# ProPrj_ProDocument_Button_Board_v3_0_202.net
KiCad netlist of a schematic drawn in EasyEDA Pro
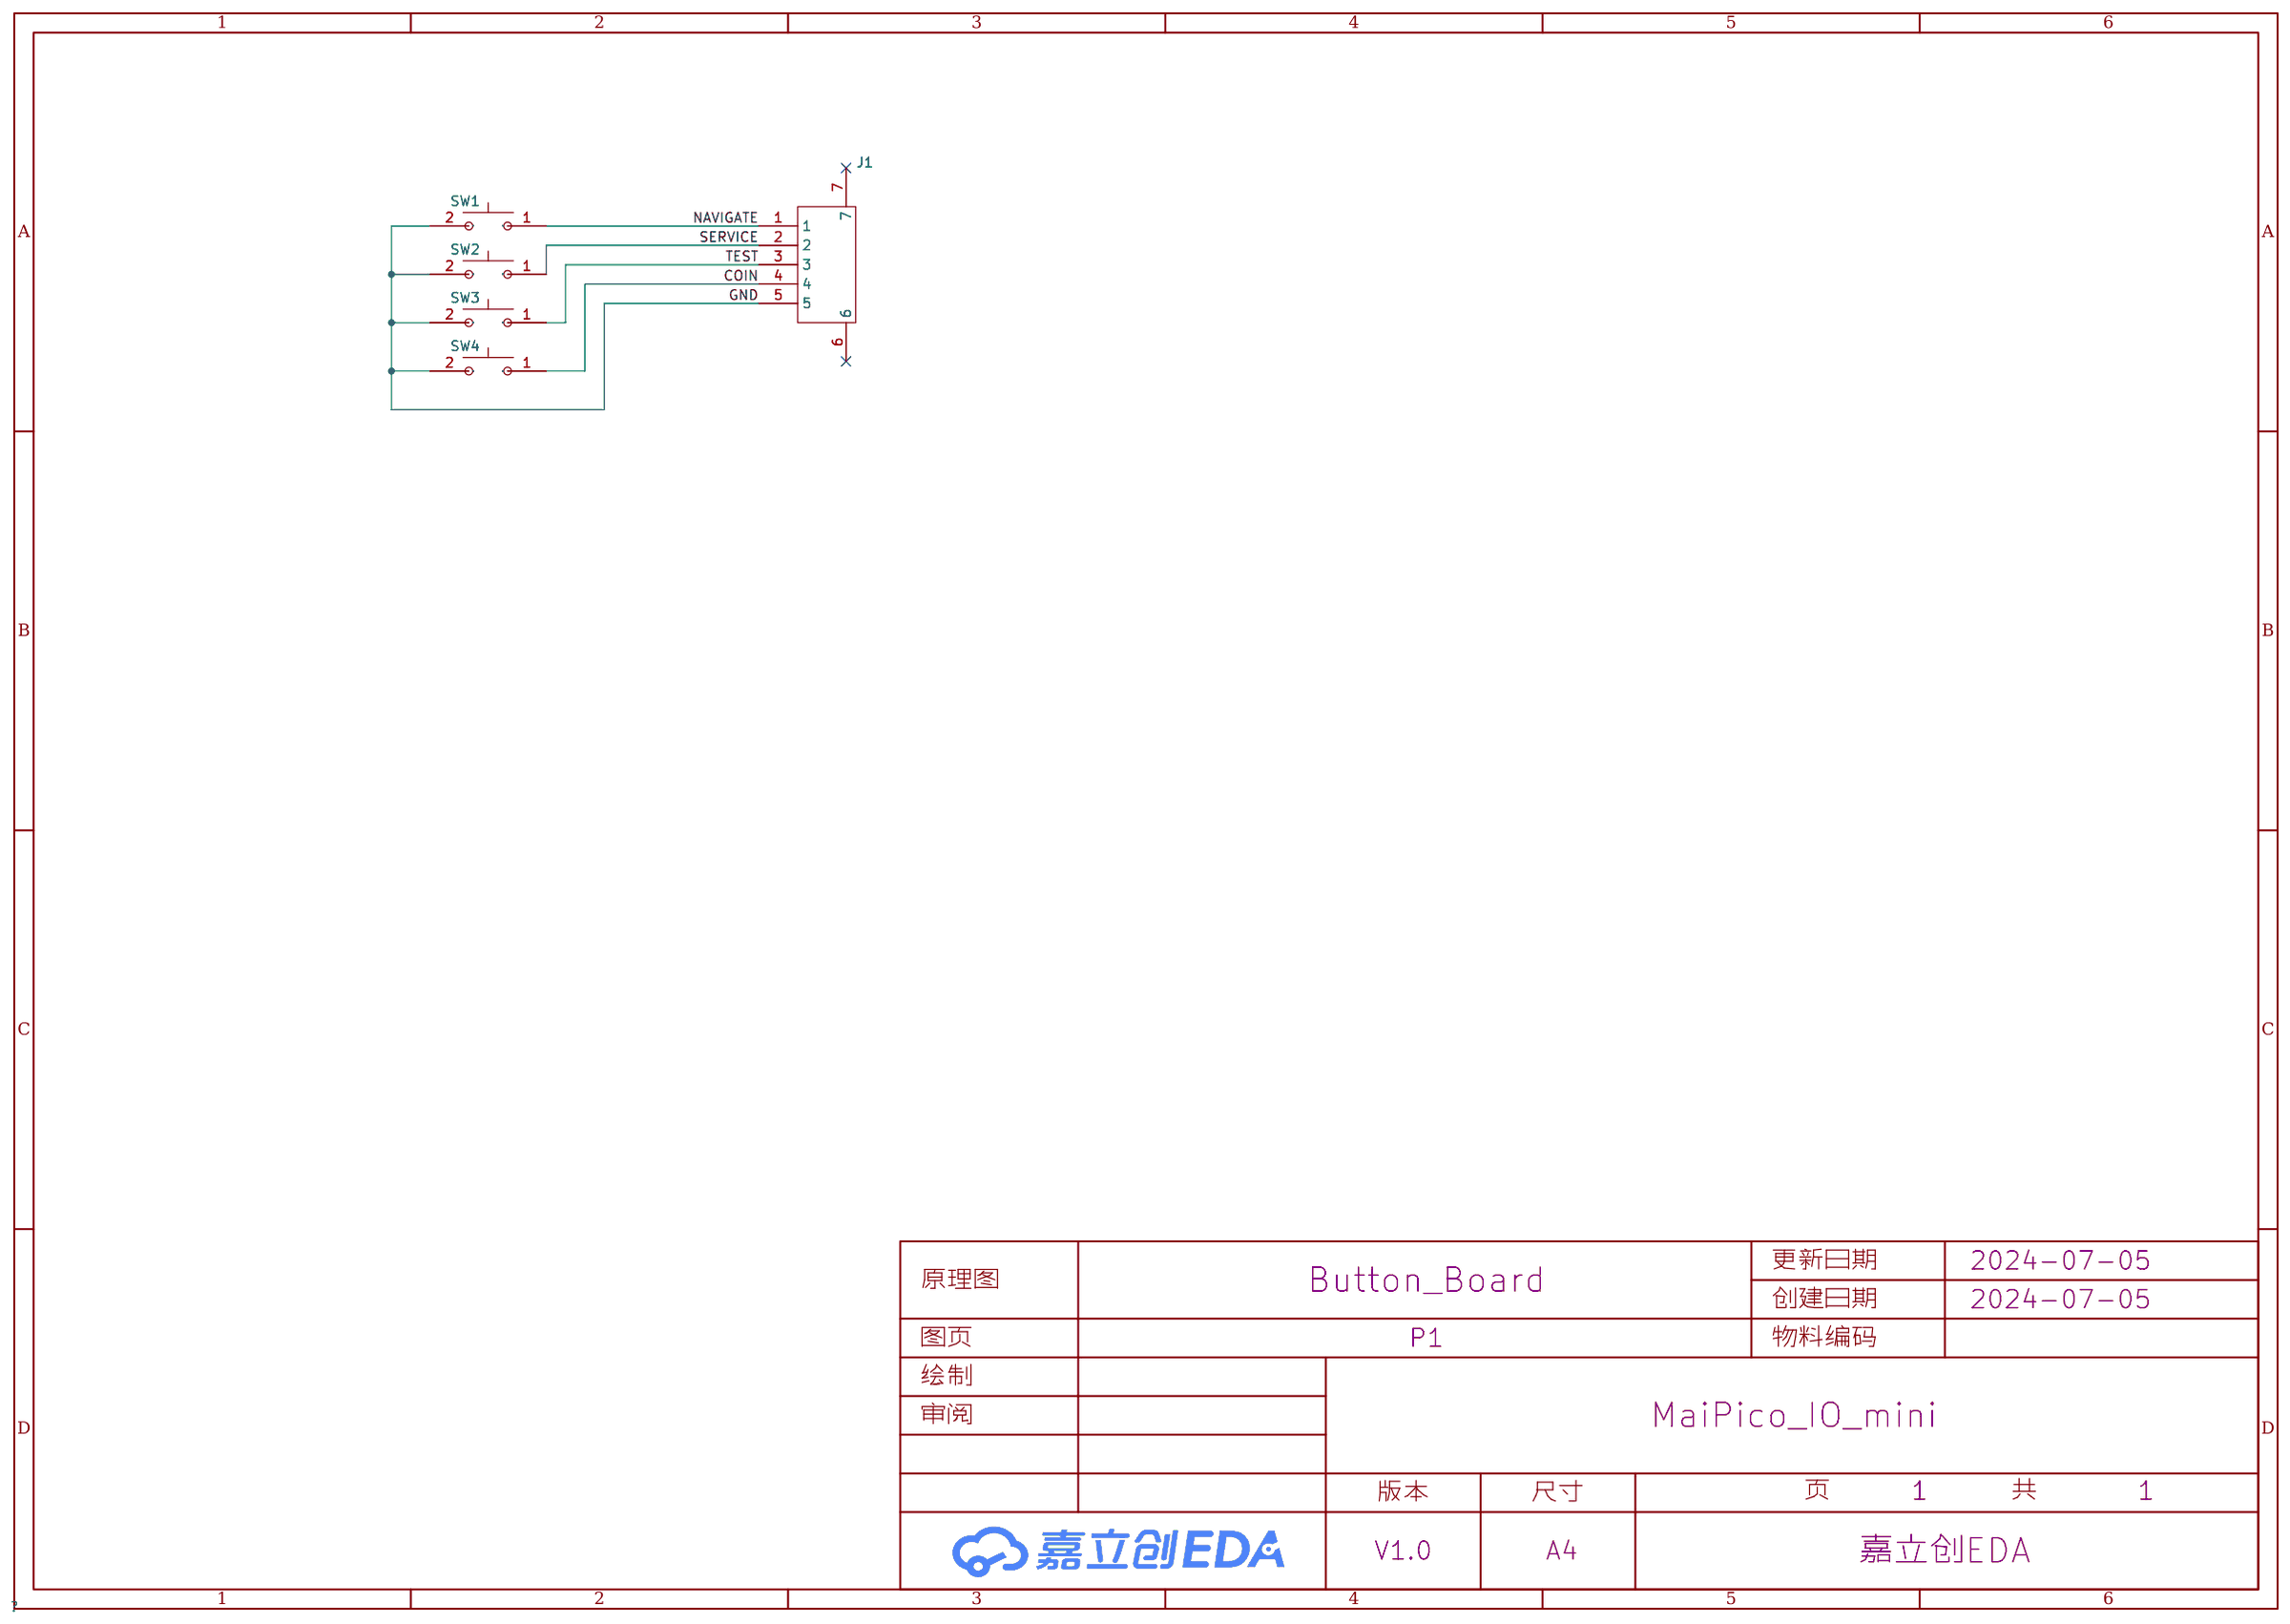
[diagram p0: schematic sheet]

(export (version "E")
  (design (tool "Eeschema 10.0.6"))
  (components
    (comp (ref "J1")
      (value "AFA01-S05FCC-00")
      (footprint "easyedapro:FPC-SMD_P1.00-5P_FGS-XJ-H2.0")
      (description "锁定特性:翻盖式;触点类型:下接;触点数量:5P;间距:1mm;安装类型:卧贴;")
      (fields (field (name "Manufacturer") "JS(钜硕电子)"))
      (libsource (lib "easyedapro") (part "AFA01-S05FCC-00"))
    )
    (comp (ref "SW1")
      (value "1TS009B-2500-5000-CT")
      (footprint "easyedapro:SW-SMD_L6.0-W6.0-P6.00-LS6.6")
      (fields (field (name "Manufacturer") "HYP(鸿源精密)"))
      (libsource (lib "easyedapro") (part "1TS009B-2500-5000"))
    )
    (comp (ref "SW2")
      (value "1TS009B-2500-5000-CT")
      (footprint "easyedapro:SW-SMD_L6.0-W6.0-P6.00-LS6.6")
      (fields (field (name "Manufacturer") "HYP(鸿源精密)"))
      (libsource (lib "easyedapro") (part "1TS009B-2500-5000"))
    )
    (comp (ref "SW3")
      (value "1TS009B-2500-5000-CT")
      (footprint "easyedapro:SW-SMD_L6.0-W6.0-P6.00-LS6.6")
      (fields (field (name "Manufacturer") "HYP(鸿源精密)"))
      (libsource (lib "easyedapro") (part "1TS009B-2500-5000"))
    )
    (comp (ref "SW4")
      (value "1TS009B-2500-5000-CT")
      (footprint "easyedapro:SW-SMD_L6.0-W6.0-P6.00-LS6.6")
      (fields (field (name "Manufacturer") "HYP(鸿源精密)"))
      (libsource (lib "easyedapro") (part "1TS009B-2500-5000"))
    )
  )
  (nets
    (net (code "1") (name "/COIN") (class "Default")
      (node (ref "J1") (pin "4") (pinfunction "4_4") (pintype "unspecified"))
      (node (ref "SW4") (pin "1") (pinfunction "1_1") (pintype "input"))
    )
    (net (code "2") (name "/GND") (class "Default")
      (node (ref "J1") (pin "5") (pinfunction "5_5") (pintype "unspecified"))
      (node (ref "SW1") (pin "2") (pinfunction "2_2") (pintype "input"))
      (node (ref "SW2") (pin "2") (pinfunction "2_2") (pintype "input"))
      (node (ref "SW3") (pin "2") (pinfunction "2_2") (pintype "input"))
      (node (ref "SW4") (pin "2") (pinfunction "2_2") (pintype "input"))
    )
    (net (code "3") (name "/NAVIGATE") (class "Default")
      (node (ref "J1") (pin "1") (pinfunction "1_1") (pintype "unspecified"))
      (node (ref "SW1") (pin "1") (pinfunction "1_1") (pintype "input"))
    )
    (net (code "4") (name "/SERVICE") (class "Default")
      (node (ref "J1") (pin "2") (pinfunction "2_2") (pintype "unspecified"))
      (node (ref "SW2") (pin "1") (pinfunction "1_1") (pintype "input"))
    )
    (net (code "5") (name "/TEST") (class "Default")
      (node (ref "J1") (pin "3") (pinfunction "3_3") (pintype "unspecified"))
      (node (ref "SW3") (pin "1") (pinfunction "1_1") (pintype "input"))
    )
    (net (code "6") (name "unconnected-(J1-Pad6)") (class "Default")
      (node (ref "J1") (pin "6") (pinfunction "6_6") (pintype "unspecified+no_connect"))
    )
    (net (code "7") (name "unconnected-(J1-Pad7)") (class "Default")
      (node (ref "J1") (pin "7") (pinfunction "7_7") (pintype "unspecified+no_connect"))
    )
  )
)
